# blinkm_mk2s.net
KiCad netlist of a schematic drawn in EAGLE
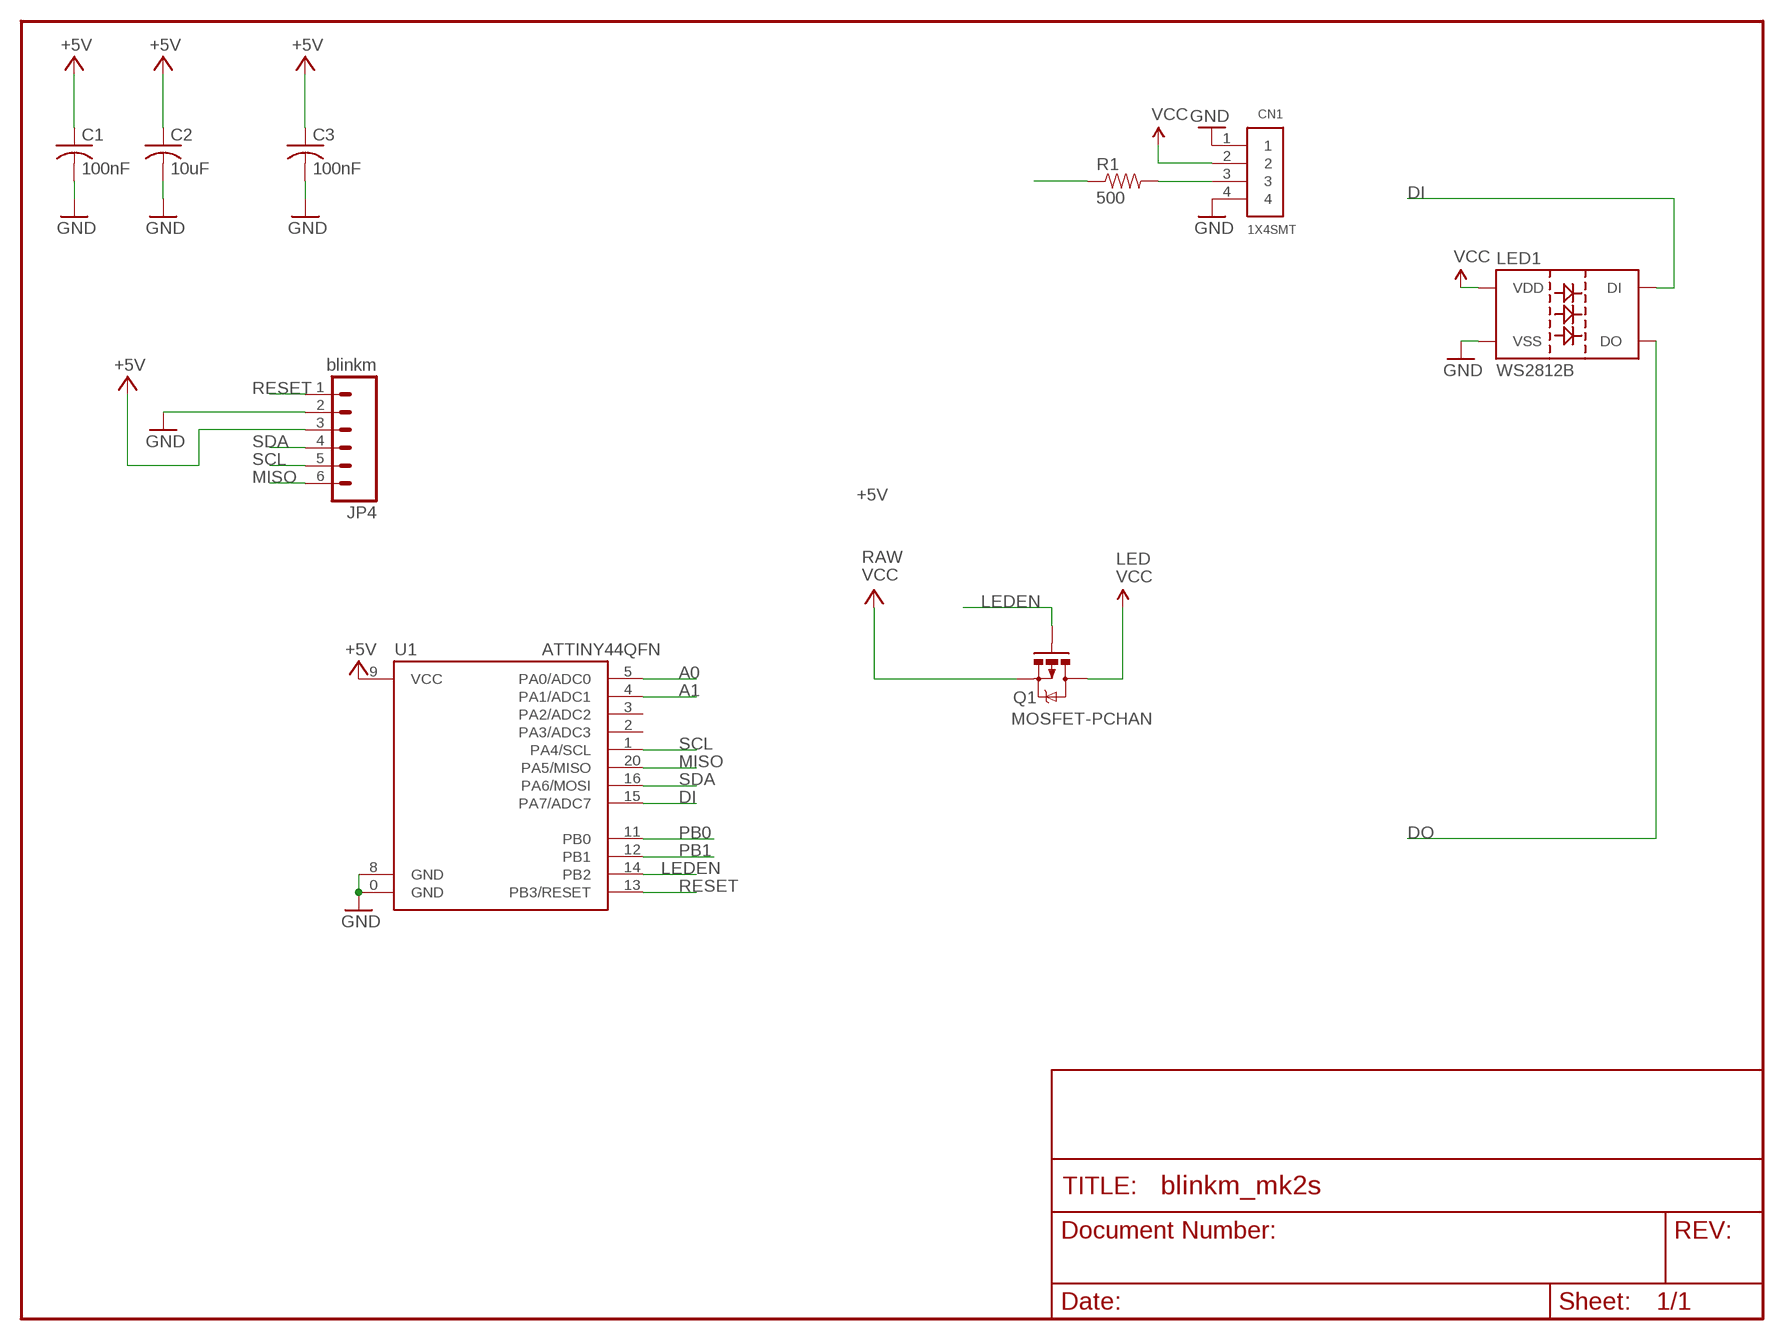
[diagram p0: schematic, sheet 1]

(export (version "E")
  (design (tool "Eeschema 10.0.6"))
  (components
    (comp (ref "C1")
      (value "100nF")
      (footprint "eagle-import:C0603")
      (libsource (lib "eagle-import") (part "C-USC0603"))
    )
    (comp (ref "C2")
      (value "10uF")
      (footprint "eagle-import:C0603")
      (libsource (lib "eagle-import") (part "C-USC0603"))
    )
    (comp (ref "C3")
      (value "100nF")
      (footprint "eagle-import:C0603")
      (libsource (lib "eagle-import") (part "C-USC0603"))
    )
    (comp (ref "CN1")
      (value "1X4SMT")
      (footprint "eagle-import:1X4-SMT")
      (libsource (lib "eagle-import") (part "1X4SMT"))
    )
    (comp (ref "JP4")
      (value "blinkm")
      (footprint "eagle-import:1X06_LOCK")
      (libsource (lib "eagle-import") (part "M06LOCK"))
    )
    (comp (ref "LED1")
      (value "WS2812B")
      (footprint "eagle-import:WS2812B")
      (libsource (lib "eagle-import") (part "WS2812B"))
    )
    (comp (ref "Q1")
      (value "MOSFET-PCHAN")
      (footprint "eagle-import:SOT23-3")
      (libsource (lib "eagle-import") (part "MOSFET-PCHANNELIRLML2244"))
    )
    (comp (ref "R1")
      (value "500")
      (footprint "eagle-import:0603-RES")
      (libsource (lib "eagle-import") (part "RESISTOR0603"))
    )
    (comp (ref "U1")
      (value "ATTINY44QFN")
      (footprint "eagle-import:QFN20")
      (libsource (lib "eagle-import") (part "ATTINY24QFN"))
    )
  )
  (nets
    (net (code "1") (name "+5V") (class "Default")
      (node (ref "C1") (pin "1") (pinfunction "1_1") (pintype "passive"))
      (node (ref "C2") (pin "1") (pinfunction "1_1") (pintype "passive"))
      (node (ref "C3") (pin "1") (pinfunction "1_1") (pintype "passive"))
      (node (ref "JP4") (pin "3") (pinfunction "3_3") (pintype "passive"))
      (node (ref "Q1") (pin "2") (pinfunction "S_2") (pintype "passive"))
      (node (ref "U1") (pin "9") (pinfunction "VCC_9") (pintype "bidirectional"))
    )
    (net (code "2") (name "/A0") (class "Default")
      (node (ref "U1") (pin "5") (pinfunction "PA0/ADC0_5") (pintype "bidirectional"))
    )
    (net (code "3") (name "/A1") (class "Default")
      (node (ref "U1") (pin "4") (pinfunction "PA1/ADC1_4") (pintype "bidirectional"))
    )
    (net (code "4") (name "/DI") (class "Default")
      (node (ref "LED1") (pin "4") (pinfunction "DI_4") (pintype "bidirectional"))
      (node (ref "U1") (pin "15") (pinfunction "PA7/ADC7_15") (pintype "bidirectional"))
    )
    (net (code "5") (name "/DO") (class "Default")
      (node (ref "LED1") (pin "2") (pinfunction "DO_2") (pintype "bidirectional"))
      (node (ref "R1") (pin "1") (pinfunction "1_1") (pintype "passive"))
    )
    (net (code "6") (name "/LEDEN") (class "Default")
      (node (ref "Q1") (pin "1") (pinfunction "G_1") (pintype "passive"))
      (node (ref "U1") (pin "14") (pinfunction "PB2_14") (pintype "bidirectional"))
    )
    (net (code "7") (name "/MISO") (class "Default")
      (node (ref "JP4") (pin "6") (pinfunction "6_6") (pintype "passive"))
      (node (ref "U1") (pin "20") (pinfunction "PA5/MISO_20") (pintype "bidirectional"))
    )
    (net (code "8") (name "/PB0") (class "Default")
      (node (ref "U1") (pin "11") (pinfunction "PB0_11") (pintype "bidirectional"))
    )
    (net (code "9") (name "/PB1") (class "Default")
      (node (ref "U1") (pin "12") (pinfunction "PB1_12") (pintype "bidirectional"))
    )
    (net (code "10") (name "/RESET") (class "Default")
      (node (ref "JP4") (pin "1") (pinfunction "1_1") (pintype "passive"))
      (node (ref "U1") (pin "13") (pinfunction "PB3/RESET_13") (pintype "bidirectional"))
    )
    (net (code "11") (name "/SCL") (class "Default")
      (node (ref "JP4") (pin "5") (pinfunction "5_5") (pintype "passive"))
      (node (ref "U1") (pin "1") (pinfunction "PA4/SCL_1") (pintype "bidirectional"))
    )
    (net (code "12") (name "/SDA") (class "Default")
      (node (ref "JP4") (pin "4") (pinfunction "4_4") (pintype "passive"))
      (node (ref "U1") (pin "16") (pinfunction "PA6/MOSI_16") (pintype "bidirectional"))
    )
    (net (code "13") (name "GND") (class "Default")
      (node (ref "C1") (pin "2") (pinfunction "2_2") (pintype "passive"))
      (node (ref "C2") (pin "2") (pinfunction "2_2") (pintype "passive"))
      (node (ref "C3") (pin "2") (pinfunction "2_2") (pintype "passive"))
      (node (ref "CN1") (pin "1") (pinfunction "1_1") (pintype "bidirectional"))
      (node (ref "CN1") (pin "4") (pinfunction "4_4") (pintype "bidirectional"))
      (node (ref "JP4") (pin "2") (pinfunction "2_2") (pintype "passive"))
      (node (ref "LED1") (pin "3") (pinfunction "VSS_3") (pintype "bidirectional"))
      (node (ref "U1") (pin "0") (pinfunction "GND_0") (pintype "bidirectional"))
      (node (ref "U1") (pin "8") (pinfunction "GND_8") (pintype "bidirectional"))
    )
    (net (code "14") (name "Net-(CN1-Pad3)") (class "Default")
      (node (ref "CN1") (pin "3") (pinfunction "3_3") (pintype "bidirectional"))
      (node (ref "R1") (pin "2") (pinfunction "2_2") (pintype "passive"))
    )
    (net (code "15") (name "VCC") (class "Default")
      (node (ref "CN1") (pin "2") (pinfunction "2_2") (pintype "bidirectional"))
      (node (ref "LED1") (pin "1") (pinfunction "VDD_1") (pintype "bidirectional"))
      (node (ref "Q1") (pin "3") (pinfunction "D_3") (pintype "passive"))
    )
    (net (code "16") (name "unconnected-(U1-PA2{slash}ADC2-Pad3)") (class "Default")
      (node (ref "U1") (pin "3") (pinfunction "PA2/ADC2_3") (pintype "bidirectional"))
    )
    (net (code "17") (name "unconnected-(U1-PA3{slash}ADC3-Pad2)") (class "Default")
      (node (ref "U1") (pin "2") (pinfunction "PA3/ADC3_2") (pintype "bidirectional"))
    )
  )
)
